# SCH_supercap_2024-08-12.net
KiCad netlist of a schematic drawn in EasyEDA
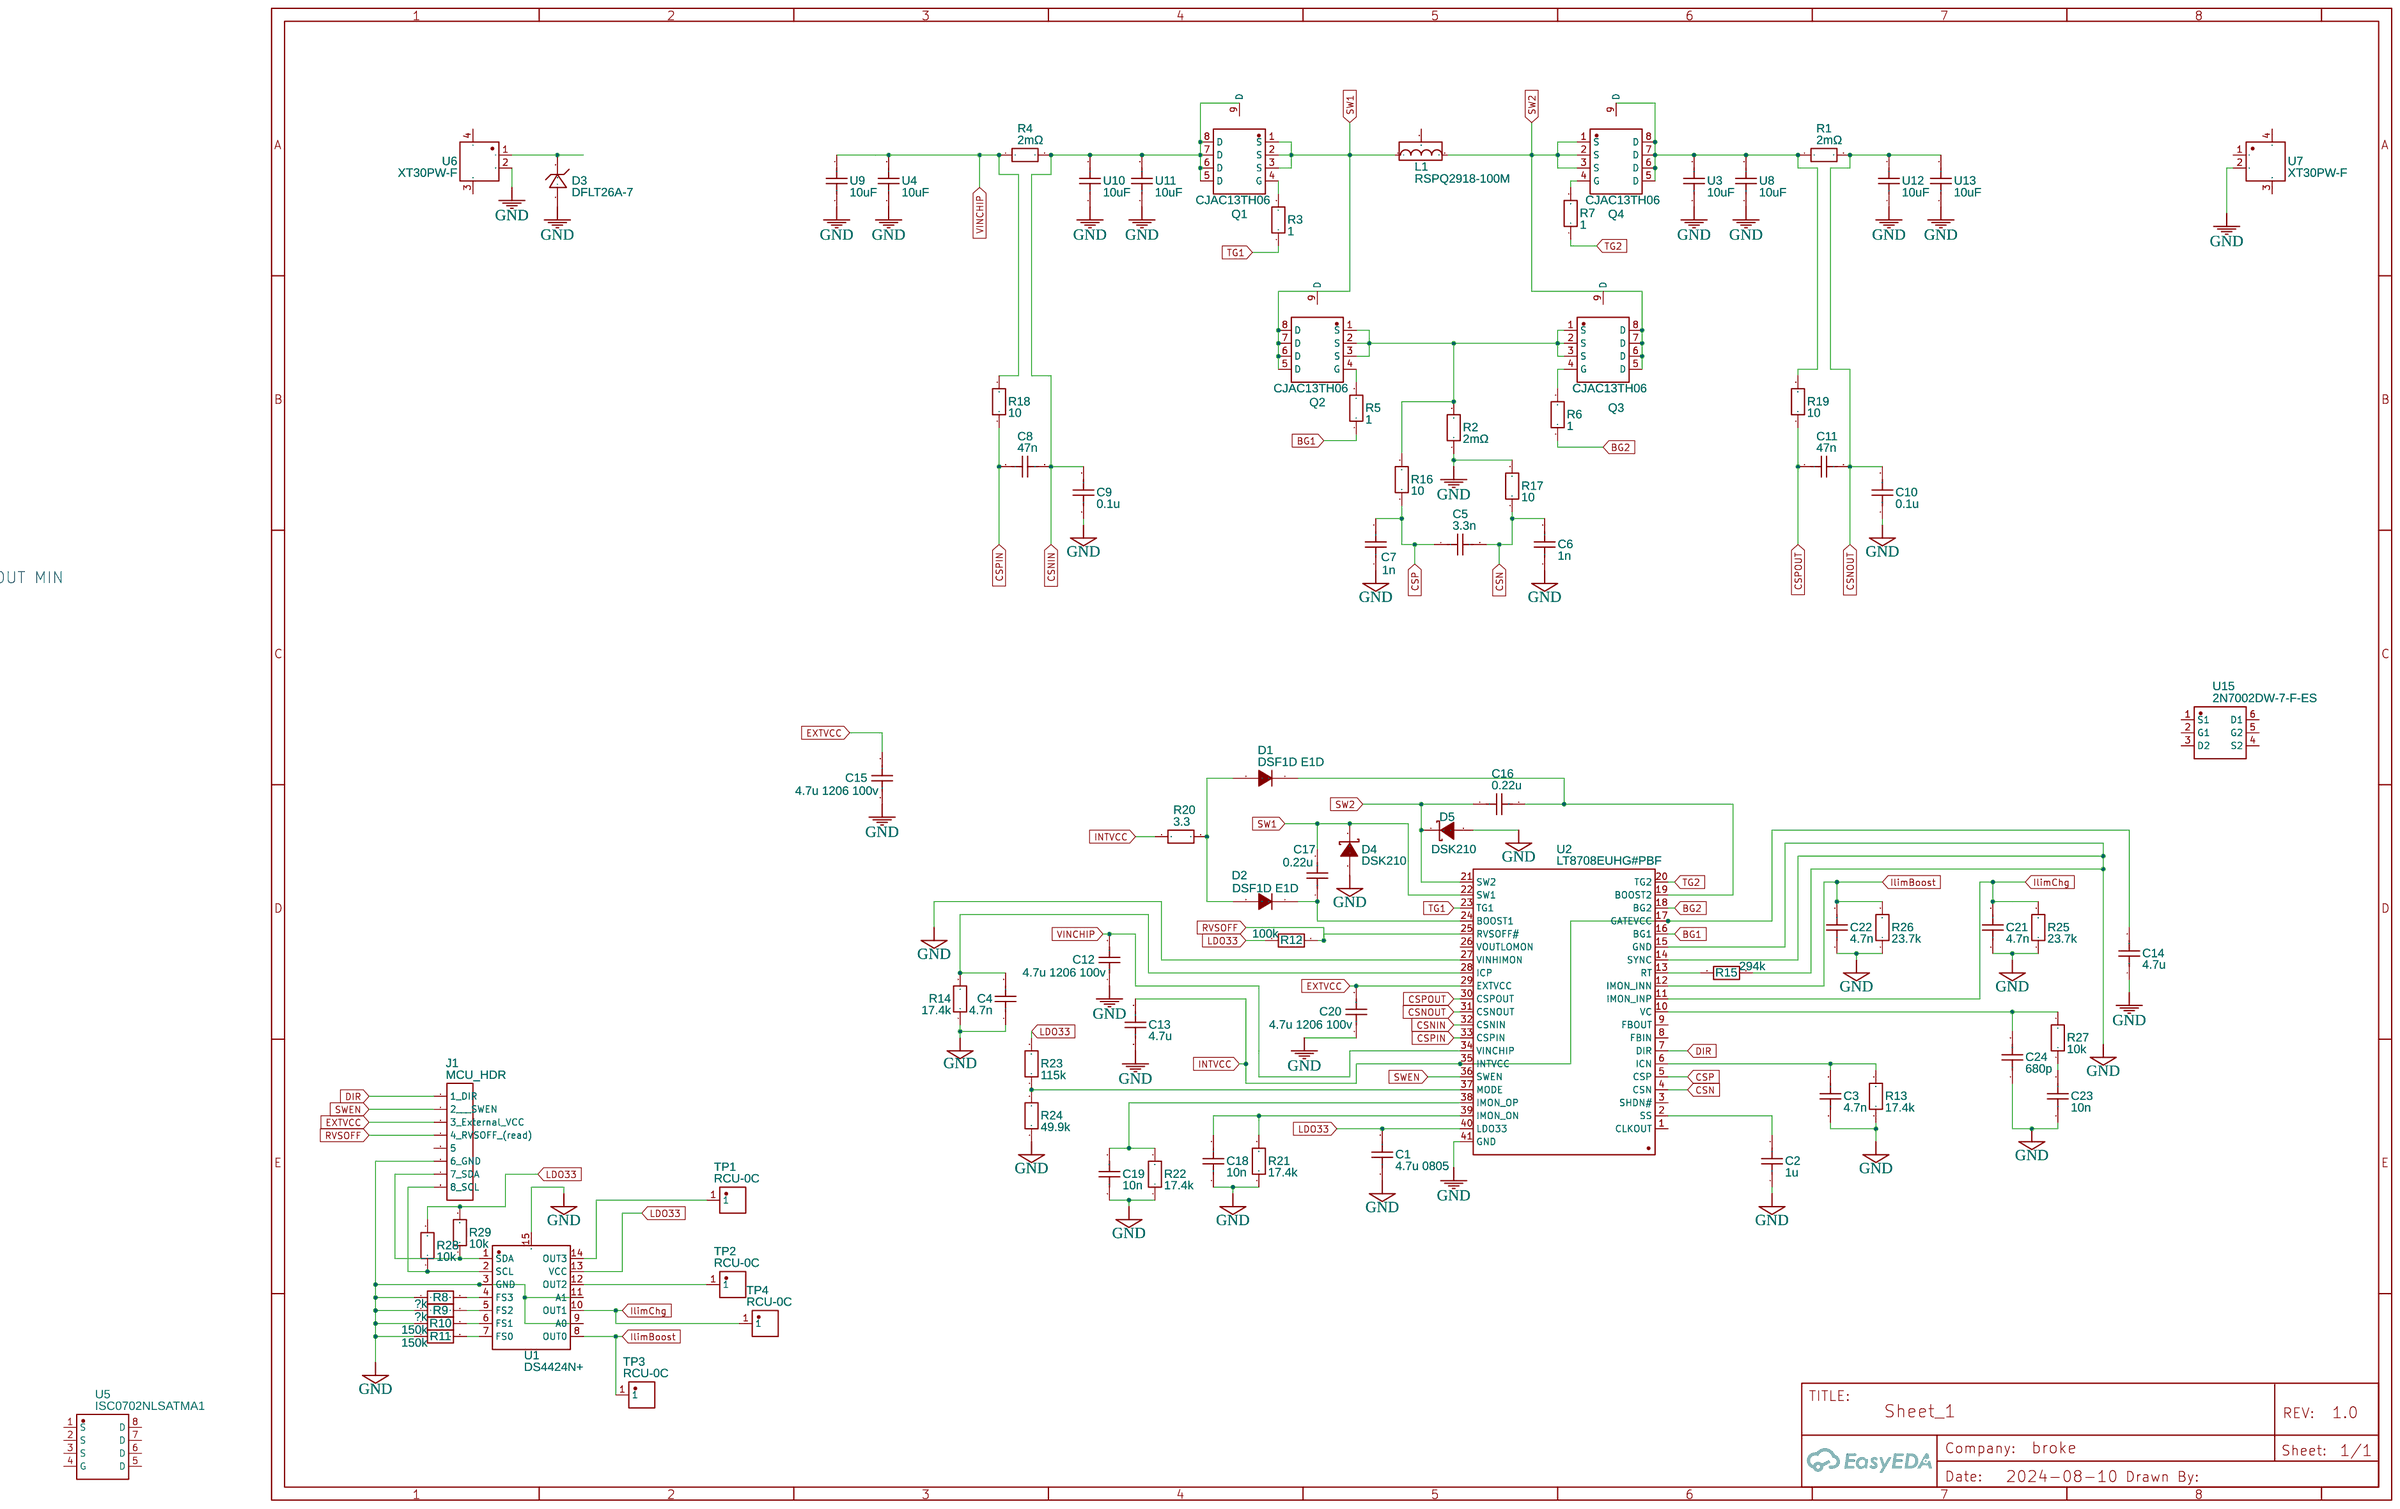
[diagram p0: schematic sheet]

(export (version "E")
  (design (tool "Eeschema 10.0.6"))
  (components
    (comp (ref "C1") (value "4.7u 0805") (libsource (lib "") (part "C_0805_US")))
    (comp (ref "C2") (value "1u") (libsource (lib "") (part "C_0603_US")))
    (comp (ref "C3") (value "4.7n") (libsource (lib "") (part "C_0603_US")))
    (comp (ref "C4") (value "4.7n") (libsource (lib "") (part "C_0603_US_1")))
    (comp (ref "C5") (value "3.3n") (libsource (lib "") (part "C_0603_US_2")))
    (comp (ref "C6") (value "1n") (libsource (lib "") (part "C_0603_US")))
    (comp (ref "C7") (value "1n") (libsource (lib "") (part "C_0603_US")))
    (comp (ref "C8") (value "47n") (libsource (lib "") (part "C_0603_US_2")))
    (comp (ref "C9") (value "0.1u") (libsource (lib "") (part "C_0603_US")))
    (comp (ref "C10") (value "0.1u") (libsource (lib "") (part "C_0603_US")))
    (comp (ref "C11") (value "47n") (libsource (lib "") (part "C_0603_US_2")))
    (comp (ref "C12") (value "4.7u 1206 100v") (libsource (lib "") (part "C_0805_US")))
    (comp (ref "C13") (value "4.7u") (libsource (lib "") (part "C_0603_US")))
    (comp (ref "C14") (value "4.7u") (libsource (lib "") (part "C_0603_US")))
    (comp (ref "C15") (value "4.7u 1206 100v") (libsource (lib "") (part "C_0805_US")))
    (comp (ref "C16") (value "0.22u") (libsource (lib "") (part "C_0603_US_2")))
    (comp (ref "C17") (value "0.22u") (libsource (lib "") (part "C_0603_US")))
    (comp (ref "C18") (value "10n") (libsource (lib "") (part "C_0603_US")))
    (comp (ref "C19") (value "10n") (libsource (lib "") (part "C_0603_US")))
    (comp (ref "C20") (value "4.7u 1206 100v") (libsource (lib "") (part "C_0805_US")))
    (comp (ref "C21") (value "4.7n") (libsource (lib "") (part "C_0603_US")))
    (comp (ref "C22") (value "4.7n") (libsource (lib "") (part "C_0603_US")))
    (comp (ref "C23") (value "10n") (libsource (lib "") (part "C_0603_US")))
    (comp (ref "C24") (value "680p") (libsource (lib "") (part "C_0603_US")))
    (comp (ref "D1")
      (value "DSF1D E1D")
      (fields (field (name "Manufacturer") "MDD(辰达半导体)"))
      (libsource (lib "") (part "DSF1D E1D"))
    )
    (comp (ref "D2")
      (value "DSF1D E1D")
      (fields (field (name "Manufacturer") "MDD(辰达半导体)"))
      (libsource (lib "") (part "DSF1D E1D"))
    )
    (comp (ref "D3")
      (value "DFLT26A-7")
      (fields (field (name "Manufacturer") "DIODES(美台)"))
      (libsource (lib "") (part "DFLT26A-7"))
    )
    (comp (ref "D4")
      (value "DSK210")
      (fields (field (name "Manufacturer") "AnBon(安邦)"))
      (libsource (lib "") (part "DSK210_1"))
    )
    (comp (ref "D5")
      (value "DSK210")
      (fields (field (name "Manufacturer") "AnBon(安邦)"))
      (libsource (lib "") (part "DSK210"))
    )
    (comp (ref "J1") (value "MCU_HDR") (libsource (lib "") (part "HDR-M-2.54_1x8")))
    (comp (ref "L1")
      (value "RSPQ2918-100M")
      (fields (field (name "Manufacturer") "Ruishen(瑞申电子)"))
      (libsource (lib "") (part "RSPQ2918-100M"))
    )
    (comp (ref "Q1")
      (value "CJAC13TH06")
      (fields (field (name "Manufacturer") "CJ(江苏长电/长晶)"))
      (libsource (lib "") (part "CJAC13TH06_1"))
    )
    (comp (ref "Q2")
      (value "CJAC13TH06")
      (fields (field (name "Manufacturer") "CJ(江苏长电/长晶)"))
      (libsource (lib "") (part "CJAC13TH06_1"))
    )
    (comp (ref "Q3")
      (value "CJAC13TH06")
      (fields (field (name "Manufacturer") "CJ(江苏长电/长晶)"))
      (libsource (lib "") (part "CJAC13TH06"))
    )
    (comp (ref "Q4")
      (value "CJAC13TH06")
      (fields (field (name "Manufacturer") "CJ(江苏长电/长晶)"))
      (libsource (lib "") (part "CJAC13TH06"))
    )
    (comp (ref "R1")
      (value "2mΩ")
      (fields (field (name "Manufacturer Part") "FCSL64R002GER") (field (name "Manufacturer") "Ohmite"))
      (libsource (lib "") (part "FCSL64R002GER_1"))
    )
    (comp (ref "R2")
      (value "2mΩ")
      (fields (field (name "Manufacturer Part") "FCSL64R002GER") (field (name "Manufacturer") "Ohmite"))
      (libsource (lib "") (part "FCSL64R002GER"))
    )
    (comp (ref "R3") (value "1") (libsource (lib "") (part "R_0603_EU_1")))
    (comp (ref "R4")
      (value "2mΩ")
      (fields (field (name "Manufacturer Part") "FCSL64R002GER") (field (name "Manufacturer") "Ohmite"))
      (libsource (lib "") (part "FCSL64R002GER_1"))
    )
    (comp (ref "R5") (value "1") (libsource (lib "") (part "R_0603_EU_1")))
    (comp (ref "R6") (value "1") (libsource (lib "") (part "R_0603_EU_1")))
    (comp (ref "R7") (value "1") (libsource (lib "") (part "R_0603_EU_1")))
    (comp (ref "R8") (value "?k") (libsource (lib "") (part "R_0603_EU")))
    (comp (ref "R9") (value "?k") (libsource (lib "") (part "R_0603_EU")))
    (comp (ref "R10") (value "150k") (libsource (lib "") (part "R_0603_EU")))
    (comp (ref "R11") (value "150k") (libsource (lib "") (part "R_0603_EU")))
    (comp (ref "R12") (value "100k") (libsource (lib "") (part "R_0603_EU")))
    (comp (ref "R13") (value "17.4k") (libsource (lib "") (part "R_0603_EU_1")))
    (comp (ref "R14") (value "17.4k") (libsource (lib "") (part "R_0603_EU_1")))
    (comp (ref "R15") (value "294k") (libsource (lib "") (part "R_0603_EU_2")))
    (comp (ref "R16") (value "10") (libsource (lib "") (part "R_0603_EU_1")))
    (comp (ref "R17") (value "10") (libsource (lib "") (part "R_0603_EU_1")))
    (comp (ref "R18") (value "10") (libsource (lib "") (part "R_0603_EU_1")))
    (comp (ref "R19") (value "10") (libsource (lib "") (part "R_0603_EU_1")))
    (comp (ref "R20") (value "3.3") (libsource (lib "") (part "R_0603_EU")))
    (comp (ref "R21") (value "17.4k") (libsource (lib "") (part "R_0603_EU_1")))
    (comp (ref "R22") (value "17.4k") (libsource (lib "") (part "R_0603_EU_1")))
    (comp (ref "R23") (value "115k") (libsource (lib "") (part "R_0603_EU_1")))
    (comp (ref "R24") (value "49.9k") (libsource (lib "") (part "R_0603_EU_1")))
    (comp (ref "R25") (value "23.7k") (libsource (lib "") (part "R_0603_EU_1")))
    (comp (ref "R26") (value "23.7k") (libsource (lib "") (part "R_0603_EU_1")))
    (comp (ref "R27") (value "10k") (libsource (lib "") (part "R_0603_EU_1")))
    (comp (ref "R28") (value "10k") (libsource (lib "") (part "R_0603_EU_1")))
    (comp (ref "R29") (value "10k") (libsource (lib "") (part "R_0603_EU_1")))
    (comp (ref "TP1") (value "RCU-0C") (libsource (lib "") (part "RCU-0C")))
    (comp (ref "TP2") (value "RCU-0C") (libsource (lib "") (part "RCU-0C")))
    (comp (ref "TP3") (value "RCU-0C") (libsource (lib "") (part "RCU-0C")))
    (comp (ref "TP4") (value "RCU-0C") (libsource (lib "") (part "RCU-0C")))
    (comp (ref "U1")
      (value "DS4424N+")
      (fields (field (name "Manufacturer") "ADI(亚德诺)/MAXIM(美信)"))
      (libsource (lib "") (part "DS4424N+"))
    )
    (comp (ref "U2")
      (value "LT8708EUHG#PBF")
      (fields (field (name "Manufacturer") "ADI(亚德诺)"))
      (libsource (lib "") (part "LT8708EUHG#PBF"))
    )
    (comp (ref "U3")
      (value "10uF")
      (fields (field (name "Manufacturer Part") "CKG57NX7R1H106M500JH") (field (name "Manufacturer") "TDK"))
      (libsource (lib "") (part "CKG57NX7R1H106M500JH"))
    )
    (comp (ref "U4")
      (value "10uF")
      (fields (field (name "Manufacturer Part") "CKG57NX7R1H106M500JH") (field (name "Manufacturer") "TDK"))
      (libsource (lib "") (part "CKG57NX7R1H106M500JH"))
    )
    (comp (ref "U5")
      (value "ISC0702NLSATMA1")
      (fields (field (name "Manufacturer") "Infineon(英飞凌)"))
      (libsource (lib "") (part "ISC0702NLSATMA1"))
    )
    (comp (ref "U6")
      (value "XT30PW-F")
      (fields (field (name "Manufacturer Part") "XT30PW-F20.G.Y") (field (name "Manufacturer") "AMASS(艾迈斯)"))
      (libsource (lib "") (part "XT30PW-F_1"))
    )
    (comp (ref "U7")
      (value "XT30PW-F")
      (fields (field (name "Manufacturer Part") "XT30PW-F20.G.Y") (field (name "Manufacturer") "AMASS(艾迈斯)"))
      (libsource (lib "") (part "XT30PW-F"))
    )
    (comp (ref "U8")
      (value "10uF")
      (fields (field (name "Manufacturer Part") "CKG57NX7R1H106M500JH") (field (name "Manufacturer") "TDK"))
      (libsource (lib "") (part "CKG57NX7R1H106M500JH"))
    )
    (comp (ref "U9")
      (value "10uF")
      (fields (field (name "Manufacturer Part") "CKG57NX7R1H106M500JH") (field (name "Manufacturer") "TDK"))
      (libsource (lib "") (part "CKG57NX7R1H106M500JH"))
    )
    (comp (ref "U10")
      (value "10uF")
      (fields (field (name "Manufacturer Part") "CKG57NX7R1H106M500JH") (field (name "Manufacturer") "TDK"))
      (libsource (lib "") (part "CKG57NX7R1H106M500JH"))
    )
    (comp (ref "U11")
      (value "10uF")
      (fields (field (name "Manufacturer Part") "CKG57NX7R1H106M500JH") (field (name "Manufacturer") "TDK"))
      (libsource (lib "") (part "CKG57NX7R1H106M500JH"))
    )
    (comp (ref "U12")
      (value "10uF")
      (fields (field (name "Manufacturer Part") "CKG57NX7R1H106M500JH") (field (name "Manufacturer") "TDK"))
      (libsource (lib "") (part "CKG57NX7R1H106M500JH"))
    )
    (comp (ref "U13")
      (value "10uF")
      (fields (field (name "Manufacturer Part") "CKG57NX7R1H106M500JH") (field (name "Manufacturer") "TDK"))
      (libsource (lib "") (part "CKG57NX7R1H106M500JH"))
    )
    (comp (ref "U15")
      (value "2N7002DW-7-F-ES")
      (fields (field (name "Manufacturer") "ElecSuper(静芯微)"))
      (libsource (lib "") (part "2N7002DW-7-F-ES"))
    )
  )
  (nets
    (net (code "1") (name "BG1") (class "Default")
      (node (ref "R5") (pin "1") (pinfunction "1_1") (pintype "unspecified"))
      (node (ref "U2") (pin "16") (pinfunction "BG1_16") (pintype "unspecified"))
    )
    (net (code "2") (name "BG2") (class "Default")
      (node (ref "R6") (pin "1") (pinfunction "1_1") (pintype "unspecified"))
      (node (ref "U2") (pin "18") (pinfunction "BG2_18") (pintype "unspecified"))
    )
    (net (code "3") (name "CSN") (class "Default")
      (node (ref "C5") (pin "2") (pinfunction "2_2") (pintype "unspecified"))
      (node (ref "C6") (pin "2") (pinfunction "2_2") (pintype "unspecified"))
      (node (ref "R17") (pin "1") (pinfunction "1_1") (pintype "unspecified"))
      (node (ref "U2") (pin "4") (pinfunction "CSN_4") (pintype "unspecified"))
    )
    (net (code "4") (name "CSNIN") (class "Default")
      (node (ref "C8") (pin "2") (pinfunction "2_2") (pintype "unspecified"))
      (node (ref "C9") (pin "2") (pinfunction "2_2") (pintype "unspecified"))
      (node (ref "Q1") (pin "5") (pinfunction "D_5") (pintype "unspecified"))
      (node (ref "Q1") (pin "6") (pinfunction "D_6") (pintype "unspecified"))
      (node (ref "Q1") (pin "7") (pinfunction "D_7") (pintype "unspecified"))
      (node (ref "Q1") (pin "8") (pinfunction "D_8") (pintype "unspecified"))
      (node (ref "R4") (pin "2") (pinfunction "2_2") (pintype "unspecified"))
      (node (ref "U10") (pin "2") (pinfunction "2_2") (pintype "unspecified"))
      (node (ref "U11") (pin "2") (pinfunction "2_2") (pintype "unspecified"))
      (node (ref "U2") (pin "32") (pinfunction "CSNIN_32") (pintype "unspecified"))
    )
    (net (code "5") (name "CSNOUT") (class "Default")
      (node (ref "C10") (pin "2") (pinfunction "2_2") (pintype "unspecified"))
      (node (ref "C11") (pin "2") (pinfunction "2_2") (pintype "unspecified"))
      (node (ref "R1") (pin "2") (pinfunction "2_2") (pintype "unspecified"))
      (node (ref "U12") (pin "2") (pinfunction "2_2") (pintype "unspecified"))
      (node (ref "U13") (pin "2") (pinfunction "2_2") (pintype "unspecified"))
      (node (ref "U2") (pin "31") (pinfunction "CSNOUT_31") (pintype "unspecified"))
    )
    (net (code "6") (name "CSP") (class "Default")
      (node (ref "C5") (pin "1") (pinfunction "1_1") (pintype "unspecified"))
      (node (ref "C7") (pin "2") (pinfunction "2_2") (pintype "unspecified"))
      (node (ref "R16") (pin "1") (pinfunction "1_1") (pintype "unspecified"))
      (node (ref "U2") (pin "5") (pinfunction "CSP_5") (pintype "unspecified"))
    )
    (net (code "7") (name "CSPIN") (class "Default")
      (node (ref "C8") (pin "1") (pinfunction "1_1") (pintype "unspecified"))
      (node (ref "R18") (pin "1") (pinfunction "1_1") (pintype "unspecified"))
      (node (ref "U2") (pin "33") (pinfunction "CSPIN_33") (pintype "unspecified"))
    )
    (net (code "8") (name "CSPOUT") (class "Default")
      (node (ref "C11") (pin "1") (pinfunction "1_1") (pintype "unspecified"))
      (node (ref "R19") (pin "1") (pinfunction "1_1") (pintype "unspecified"))
      (node (ref "U2") (pin "30") (pinfunction "CSPOUT_30") (pintype "unspecified"))
    )
    (net (code "9") (name "DIR") (class "Default")
      (node (ref "J1") (pin "1") (pinfunction "1_DIR_1") (pintype "unspecified"))
      (node (ref "U2") (pin "7") (pinfunction "DIR_7") (pintype "unspecified"))
    )
    (net (code "10") (name "EXTVCC") (class "Default")
      (node (ref "C15") (pin "2") (pinfunction "2_2") (pintype "unspecified"))
      (node (ref "C20") (pin "2") (pinfunction "2_2") (pintype "unspecified"))
      (node (ref "J1") (pin "3") (pinfunction "3_External_VCC_3") (pintype "unspecified"))
      (node (ref "U2") (pin "29") (pinfunction "EXTVCC_29") (pintype "unspecified"))
    )
    (net (code "11") (name "GND") (class "Default")
      (node (ref "C1") (pin "1") (pinfunction "1_1") (pintype "unspecified"))
      (node (ref "C10") (pin "1") (pinfunction "1_1") (pintype "unspecified"))
      (node (ref "C12") (pin "1") (pinfunction "1_1") (pintype "unspecified"))
      (node (ref "C13") (pin "1") (pinfunction "1_1") (pintype "unspecified"))
      (node (ref "C14") (pin "1") (pinfunction "1_1") (pintype "unspecified"))
      (node (ref "C15") (pin "1") (pinfunction "1_1") (pintype "unspecified"))
      (node (ref "C18") (pin "1") (pinfunction "1_1") (pintype "unspecified"))
      (node (ref "C19") (pin "1") (pinfunction "1_1") (pintype "unspecified"))
      (node (ref "C2") (pin "1") (pinfunction "1_1") (pintype "unspecified"))
      (node (ref "C20") (pin "1") (pinfunction "1_1") (pintype "unspecified"))
      (node (ref "C21") (pin "1") (pinfunction "1_1") (pintype "unspecified"))
      (node (ref "C22") (pin "1") (pinfunction "1_1") (pintype "unspecified"))
      (node (ref "C23") (pin "1") (pinfunction "1_1") (pintype "unspecified"))
      (node (ref "C24") (pin "1") (pinfunction "1_1") (pintype "unspecified"))
      (node (ref "C3") (pin "1") (pinfunction "1_1") (pintype "unspecified"))
      (node (ref "C4") (pin "1") (pinfunction "1_1") (pintype "unspecified"))
      (node (ref "C6") (pin "1") (pinfunction "1_1") (pintype "unspecified"))
      (node (ref "C7") (pin "1") (pinfunction "1_1") (pintype "unspecified"))
      (node (ref "C9") (pin "1") (pinfunction "1_1") (pintype "unspecified"))
      (node (ref "D3") (pin "2") (pinfunction "A_2") (pintype "unspecified"))
      (node (ref "D4") (pin "2") (pinfunction "A_2") (pintype "unspecified"))
      (node (ref "D5") (pin "2") (pinfunction "A_2") (pintype "unspecified"))
      (node (ref "J1") (pin "6") (pinfunction "6_GND_6") (pintype "unspecified"))
      (node (ref "R10") (pin "1") (pinfunction "1_1") (pintype "unspecified"))
      (node (ref "R11") (pin "1") (pinfunction "1_1") (pintype "unspecified"))
      (node (ref "R13") (pin "1") (pinfunction "1_1") (pintype "unspecified"))
      (node (ref "R14") (pin "1") (pinfunction "1_1") (pintype "unspecified"))
      (node (ref "R15") (pin "1") (pinfunction "1_1") (pintype "unspecified"))
      (node (ref "R17") (pin "2") (pinfunction "2_2") (pintype "unspecified"))
      (node (ref "R2") (pin "1") (pinfunction "1_1") (pintype "unspecified"))
      (node (ref "R21") (pin "1") (pinfunction "1_1") (pintype "unspecified"))
      (node (ref "R22") (pin "1") (pinfunction "1_1") (pintype "unspecified"))
      (node (ref "R24") (pin "1") (pinfunction "1_1") (pintype "unspecified"))
      (node (ref "R25") (pin "1") (pinfunction "1_1") (pintype "unspecified"))
      (node (ref "R26") (pin "1") (pinfunction "1_1") (pintype "unspecified"))
      (node (ref "R8") (pin "1") (pinfunction "1_1") (pintype "unspecified"))
      (node (ref "R9") (pin "1") (pinfunction "1_1") (pintype "unspecified"))
      (node (ref "U1") (pin "11") (pinfunction "A1_11") (pintype "unspecified"))
      (node (ref "U1") (pin "15") (pinfunction "EP_15") (pintype "unspecified"))
      (node (ref "U1") (pin "3") (pinfunction "GND_3") (pintype "unspecified"))
      (node (ref "U1") (pin "9") (pinfunction "A0_9") (pintype "unspecified"))
      (node (ref "U10") (pin "1") (pinfunction "1_1") (pintype "unspecified"))
      (node (ref "U11") (pin "1") (pinfunction "1_1") (pintype "unspecified"))
      (node (ref "U12") (pin "1") (pinfunction "1_1") (pintype "unspecified"))
      (node (ref "U13") (pin "1") (pinfunction "1_1") (pintype "unspecified"))
      (node (ref "U2") (pin "14") (pinfunction "SYNC_14") (pintype "unspecified"))
      (node (ref "U2") (pin "15") (pinfunction "GND_15") (pintype "unspecified"))
      (node (ref "U2") (pin "27") (pinfunction "VINHIMON_27") (pintype "unspecified"))
      (node (ref "U2") (pin "41") (pinfunction "GND_41") (pintype "unspecified"))
      (node (ref "U3") (pin "1") (pinfunction "1_1") (pintype "unspecified"))
      (node (ref "U4") (pin "1") (pinfunction "1_1") (pintype "unspecified"))
      (node (ref "U6") (pin "2") (pinfunction "2_2") (pintype "unspecified"))
      (node (ref "U7") (pin "2") (pinfunction "2_2") (pintype "unspecified"))
      (node (ref "U8") (pin "1") (pinfunction "1_1") (pintype "unspecified"))
      (node (ref "U9") (pin "1") (pinfunction "1_1") (pintype "unspecified"))
    )
    (net (code "12") (name "INTVCC") (class "Default")
      (node (ref "C13") (pin "2") (pinfunction "2_2") (pintype "unspecified"))
      (node (ref "C14") (pin "2") (pinfunction "2_2") (pintype "unspecified"))
      (node (ref "R20") (pin "1") (pinfunction "1_1") (pintype "unspecified"))
      (node (ref "U2") (pin "17") (pinfunction "GATEVCC_17") (pintype "unspecified"))
      (node (ref "U2") (pin "35") (pinfunction "INTVCC_35") (pintype "unspecified"))
    )
    (net (code "13") (name "IlimBoost") (class "Default")
      (node (ref "C22") (pin "2") (pinfunction "2_2") (pintype "unspecified"))
      (node (ref "R26") (pin "2") (pinfunction "2_2") (pintype "unspecified"))
      (node (ref "TP3") (pin "1") (pinfunction "1_1") (pintype "unspecified"))
      (node (ref "U1") (pin "8") (pinfunction "OUT0_8") (pintype "unspecified"))
      (node (ref "U2") (pin "12") (pinfunction "IMON_INN_12") (pintype "unspecified"))
    )
    (net (code "14") (name "IlimChg") (class "Default")
      (node (ref "C21") (pin "2") (pinfunction "2_2") (pintype "unspecified"))
      (node (ref "R25") (pin "2") (pinfunction "2_2") (pintype "unspecified"))
      (node (ref "TP4") (pin "1") (pinfunction "1_1") (pintype "unspecified"))
      (node (ref "U1") (pin "10") (pinfunction "OUT1_10") (pintype "unspecified"))
      (node (ref "U2") (pin "11") (pinfunction "IMON_INP_11") (pintype "unspecified"))
    )
    (net (code "15") (name "LDO33") (class "Default")
      (node (ref "C1") (pin "2") (pinfunction "2_2") (pintype "unspecified"))
      (node (ref "R12") (pin "1") (pinfunction "1_1") (pintype "unspecified"))
      (node (ref "R23") (pin "2") (pinfunction "2_2") (pintype "unspecified"))
      (node (ref "R28") (pin "2") (pinfunction "2_2") (pintype "unspecified"))
      (node (ref "R29") (pin "2") (pinfunction "2_2") (pintype "unspecified"))
      (node (ref "U1") (pin "13") (pinfunction "VCC_13") (pintype "unspecified"))
      (node (ref "U2") (pin "40") (pinfunction "LDO33_40") (pintype "unspecified"))
    )
    (net (code "16") (name "Net-(C23-Pad2)") (class "Default")
      (node (ref "C23") (pin "2") (pinfunction "2_2") (pintype "unspecified"))
      (node (ref "R27") (pin "1") (pinfunction "1_1") (pintype "unspecified"))
    )
    (net (code "17") (name "Net-(D1-Pad2)") (class "Default")
      (node (ref "D1") (pin "2") (pinfunction "2_2") (pintype "unspecified"))
      (node (ref "D2") (pin "2") (pinfunction "2_2") (pintype "unspecified"))
      (node (ref "R20") (pin "2") (pinfunction "2_2") (pintype "unspecified"))
    )
    (net (code "18") (name "Net-(D3-C)") (class "Default")
      (node (ref "D3") (pin "1") (pinfunction "C_1") (pintype "unspecified"))
      (node (ref "U6") (pin "1") (pinfunction "1_1") (pintype "unspecified"))
    )
    (net (code "19") (name "Net-(J1-7_SDA)") (class "Default")
      (node (ref "J1") (pin "7") (pinfunction "7_SDA_7") (pintype "unspecified"))
      (node (ref "R29") (pin "1") (pinfunction "1_1") (pintype "unspecified"))
      (node (ref "U1") (pin "1") (pinfunction "SDA_1") (pintype "unspecified"))
    )
    (net (code "20") (name "Net-(J1-8_SCL)") (class "Default")
      (node (ref "J1") (pin "8") (pinfunction "8_SCL_8") (pintype "unspecified"))
      (node (ref "R28") (pin "1") (pinfunction "1_1") (pintype "unspecified"))
      (node (ref "U1") (pin "2") (pinfunction "SCL_2") (pintype "unspecified"))
    )
    (net (code "21") (name "Net-(Q1-G)") (class "Default")
      (node (ref "Q1") (pin "4") (pinfunction "G_4") (pintype "unspecified"))
      (node (ref "R3") (pin "2") (pinfunction "2_2") (pintype "unspecified"))
    )
    (net (code "22") (name "Net-(Q2-G)") (class "Default")
      (node (ref "Q2") (pin "4") (pinfunction "G_4") (pintype "unspecified"))
      (node (ref "R5") (pin "2") (pinfunction "2_2") (pintype "unspecified"))
    )
    (net (code "23") (name "Net-(Q2-S-Pad1)") (class "Default")
      (node (ref "Q2") (pin "1") (pinfunction "S_1") (pintype "unspecified"))
      (node (ref "Q2") (pin "2") (pinfunction "S_2") (pintype "unspecified"))
      (node (ref "Q2") (pin "3") (pinfunction "S_3") (pintype "unspecified"))
      (node (ref "Q3") (pin "1") (pinfunction "S_1") (pintype "unspecified"))
      (node (ref "Q3") (pin "2") (pinfunction "S_2") (pintype "unspecified"))
      (node (ref "Q3") (pin "3") (pinfunction "S_3") (pintype "unspecified"))
      (node (ref "R16") (pin "2") (pinfunction "2_2") (pintype "unspecified"))
      (node (ref "R2") (pin "2") (pinfunction "2_2") (pintype "unspecified"))
    )
    (net (code "24") (name "Net-(Q3-G)") (class "Default")
      (node (ref "Q3") (pin "4") (pinfunction "G_4") (pintype "unspecified"))
      (node (ref "R6") (pin "2") (pinfunction "2_2") (pintype "unspecified"))
    )
    (net (code "25") (name "Net-(Q4-D-Pad5)") (class "Default")
      (node (ref "Q4") (pin "5") (pinfunction "D_5") (pintype "unspecified"))
      (node (ref "Q4") (pin "6") (pinfunction "D_6") (pintype "unspecified"))
      (node (ref "Q4") (pin "7") (pinfunction "D_7") (pintype "unspecified"))
      (node (ref "Q4") (pin "8") (pinfunction "D_8") (pintype "unspecified"))
      (node (ref "R1") (pin "1") (pinfunction "1_1") (pintype "unspecified"))
      (node (ref "R19") (pin "2") (pinfunction "2_2") (pintype "unspecified"))
      (node (ref "U3") (pin "2") (pinfunction "2_2") (pintype "unspecified"))
      (node (ref "U8") (pin "2") (pinfunction "2_2") (pintype "unspecified"))
    )
    (net (code "26") (name "Net-(Q4-G)") (class "Default")
      (node (ref "Q4") (pin "4") (pinfunction "G_4") (pintype "unspecified"))
      (node (ref "R7") (pin "2") (pinfunction "2_2") (pintype "unspecified"))
    )
    (net (code "27") (name "Net-(U1-FS0)") (class "Default")
      (node (ref "R11") (pin "2") (pinfunction "2_2") (pintype "unspecified"))
      (node (ref "U1") (pin "7") (pinfunction "FS0_7") (pintype "unspecified"))
    )
    (net (code "28") (name "Net-(U1-FS1)") (class "Default")
      (node (ref "R10") (pin "2") (pinfunction "2_2") (pintype "unspecified"))
      (node (ref "U1") (pin "6") (pinfunction "FS1_6") (pintype "unspecified"))
    )
    (net (code "29") (name "Net-(U1-FS2)") (class "Default")
      (node (ref "R9") (pin "2") (pinfunction "2_2") (pintype "unspecified"))
      (node (ref "U1") (pin "5") (pinfunction "FS2_5") (pintype "unspecified"))
    )
    (net (code "30") (name "Net-(U1-FS3)") (class "Default")
      (node (ref "R8") (pin "2") (pinfunction "2_2") (pintype "unspecified"))
      (node (ref "U1") (pin "4") (pinfunction "FS3_4") (pintype "unspecified"))
    )
    (net (code "31") (name "Net-(U1-OUT2)") (class "Default")
      (node (ref "TP2") (pin "1") (pinfunction "1_1") (pintype "unspecified"))
      (node (ref "U1") (pin "12") (pinfunction "OUT2_12") (pintype "unspecified"))
    )
    (net (code "32") (name "Net-(U1-OUT3)") (class "Default")
      (node (ref "TP1") (pin "1") (pinfunction "1_1") (pintype "unspecified"))
      (node (ref "U1") (pin "14") (pinfunction "OUT3_14") (pintype "unspecified"))
    )
    (net (code "33") (name "Net-(U2-BOOST1)") (class "Default")
      (node (ref "C17") (pin "1") (pinfunction "1_1") (pintype "unspecified"))
      (node (ref "D2") (pin "1") (pinfunction "1_1") (pintype "unspecified"))
      (node (ref "U2") (pin "24") (pinfunction "BOOST1_24") (pintype "unspecified"))
    )
    (net (code "34") (name "Net-(U2-BOOST2)") (class "Default")
      (node (ref "C16") (pin "2") (pinfunction "2_2") (pintype "unspecified"))
      (node (ref "D1") (pin "1") (pinfunction "1_1") (pintype "unspecified"))
      (node (ref "U2") (pin "19") (pinfunction "BOOST2_19") (pintype "unspecified"))
    )
    (net (code "35") (name "Net-(U2-ICN)") (class "Default")
      (node (ref "C3") (pin "2") (pinfunction "2_2") (pintype "unspecified"))
      (node (ref "R13") (pin "2") (pinfunction "2_2") (pintype "unspecified"))
      (node (ref "U2") (pin "6") (pinfunction "ICN_6") (pintype "unspecified"))
    )
    (net (code "36") (name "Net-(U2-ICP)") (class "Default")
      (node (ref "C4") (pin "2") (pinfunction "2_2") (pintype "unspecified"))
      (node (ref "R14") (pin "2") (pinfunction "2_2") (pintype "unspecified"))
      (node (ref "U2") (pin "28") (pinfunction "ICP_28") (pintype "unspecified"))
    )
    (net (code "37") (name "Net-(U2-IMON_ON)") (class "Default")
      (node (ref "C18") (pin "2") (pinfunction "2_2") (pintype "unspecified"))
      (node (ref "R21") (pin "2") (pinfunction "2_2") (pintype "unspecified"))
      (node (ref "U2") (pin "39") (pinfunction "IMON_ON_39") (pintype "unspecified"))
    )
    (net (code "38") (name "Net-(U2-IMON_OP)") (class "Default")
      (node (ref "C19") (pin "2") (pinfunction "2_2") (pintype "unspecified"))
      (node (ref "R22") (pin "2") (pinfunction "2_2") (pintype "unspecified"))
      (node (ref "U2") (pin "38") (pinfunction "IMON_OP_38") (pintype "unspecified"))
    )
    (net (code "39") (name "Net-(U2-MODE)") (class "Default")
      (node (ref "R23") (pin "1") (pinfunction "1_1") (pintype "unspecified"))
      (node (ref "R24") (pin "2") (pinfunction "2_2") (pintype "unspecified"))
      (node (ref "U2") (pin "37") (pinfunction "MODE_37") (pintype "unspecified"))
    )
    (net (code "40") (name "Net-(U2-RT)") (class "Default")
      (node (ref "R15") (pin "2") (pinfunction "2_2") (pintype "unspecified"))
      (node (ref "U2") (pin "13") (pinfunction "RT_13") (pintype "unspecified"))
    )
    (net (code "41") (name "Net-(U2-SS)") (class "Default")
      (node (ref "C2") (pin "2") (pinfunction "2_2") (pintype "unspecified"))
      (node (ref "U2") (pin "2") (pinfunction "SS_2") (pintype "unspecified"))
    )
    (net (code "42") (name "Net-(U2-VC)") (class "Default")
      (node (ref "C24") (pin "2") (pinfunction "2_2") (pintype "unspecified"))
      (node (ref "R27") (pin "2") (pinfunction "2_2") (pintype "unspecified"))
      (node (ref "U2") (pin "10") (pinfunction "VC_10") (pintype "unspecified"))
    )
    (net (code "43") (name "RVSOFF") (class "Default")
      (node (ref "J1") (pin "4") (pinfunction "4_RVSOFF_(read)_4") (pintype "unspecified"))
      (node (ref "R12") (pin "2") (pinfunction "2_2") (pintype "unspecified"))
      (node (ref "U2") (pin "25") (pinfunction "RVSOFF#_25") (pintype "unspecified"))
    )
    (net (code "44") (name "SW1") (class "Default")
      (node (ref "C17") (pin "2") (pinfunction "2_2") (pintype "unspecified"))
      (node (ref "D4") (pin "1") (pinfunction "C_1") (pintype "unspecified"))
      (node (ref "L1") (pin "1") (pinfunction "1_1") (pintype "unspecified"))
      (node (ref "Q1") (pin "1") (pinfunction "S_1") (pintype "unspecified"))
      (node (ref "Q1") (pin "2") (pinfunction "S_2") (pintype "unspecified"))
      (node (ref "Q1") (pin "3") (pinfunction "S_3") (pintype "unspecified"))
      (node (ref "Q2") (pin "5") (pinfunction "D_5") (pintype "unspecified"))
      (node (ref "Q2") (pin "6") (pinfunction "D_6") (pintype "unspecified"))
      (node (ref "Q2") (pin "7") (pinfunction "D_7") (pintype "unspecified"))
      (node (ref "Q2") (pin "8") (pinfunction "D_8") (pintype "unspecified"))
      (node (ref "U2") (pin "22") (pinfunction "SW1_22") (pintype "unspecified"))
    )
    (net (code "45") (name "SW2") (class "Default")
      (node (ref "C16") (pin "1") (pinfunction "1_1") (pintype "unspecified"))
      (node (ref "D5") (pin "1") (pinfunction "C_1") (pintype "unspecified"))
      (node (ref "L1") (pin "2") (pinfunction "2_2") (pintype "unspecified"))
      (node (ref "Q3") (pin "5") (pinfunction "D_5") (pintype "unspecified"))
      (node (ref "Q3") (pin "6") (pinfunction "D_6") (pintype "unspecified"))
      (node (ref "Q3") (pin "7") (pinfunction "D_7") (pintype "unspecified"))
      (node (ref "Q3") (pin "8") (pinfunction "D_8") (pintype "unspecified"))
      (node (ref "Q4") (pin "1") (pinfunction "S_1") (pintype "unspecified"))
      (node (ref "Q4") (pin "2") (pinfunction "S_2") (pintype "unspecified"))
      (node (ref "Q4") (pin "3") (pinfunction "S_3") (pintype "unspecified"))
      (node (ref "U2") (pin "21") (pinfunction "SW2_21") (pintype "unspecified"))
    )
    (net (code "46") (name "SWEN") (class "Default")
      (node (ref "J1") (pin "2") (pinfunction "2___SWEN_2") (pintype "unspecified"))
      (node (ref "U2") (pin "36") (pinfunction "SWEN_36") (pintype "unspecified"))
    )
    (net (code "47") (name "TG1") (class "Default")
      (node (ref "R3") (pin "1") (pinfunction "1_1") (pintype "unspecified"))
      (node (ref "U2") (pin "23") (pinfunction "TG1_23") (pintype "unspecified"))
    )
    (net (code "48") (name "TG2") (class "Default")
      (node (ref "R7") (pin "1") (pinfunction "1_1") (pintype "unspecified"))
      (node (ref "U2") (pin "20") (pinfunction "TG2_20") (pintype "unspecified"))
    )
    (net (code "49") (name "VINCHIP") (class "Default")
      (node (ref "C12") (pin "2") (pinfunction "2_2") (pintype "unspecified"))
      (node (ref "R18") (pin "2") (pinfunction "2_2") (pintype "unspecified"))
      (node (ref "R4") (pin "1") (pinfunction "1_1") (pintype "unspecified"))
      (node (ref "U2") (pin "34") (pinfunction "VINCHIP_34") (pintype "unspecified"))
      (node (ref "U4") (pin "2") (pinfunction "2_2") (pintype "unspecified"))
      (node (ref "U9") (pin "2") (pinfunction "2_2") (pintype "unspecified"))
    )
    (net (code "50") (name "unconnected-(J1-Pad5)") (class "Default")
      (node (ref "J1") (pin "5") (pinfunction "5_5") (pintype "unspecified"))
    )
    (net (code "51") (name "unconnected-(L1-NC-Pad3)") (class "Default")
      (node (ref "L1") (pin "3") (pinfunction "NC_3") (pintype "unspecified"))
    )
    (net (code "52") (name "unconnected-(Q1-D-Pad9)") (class "Default")
      (node (ref "Q1") (pin "9") (pinfunction "D_9") (pintype "unspecified"))
    )
    (net (code "53") (name "unconnected-(Q2-D-Pad9)") (class "Default")
      (node (ref "Q2") (pin "9") (pinfunction "D_9") (pintype "unspecified"))
    )
    (net (code "54") (name "unconnected-(Q3-D-Pad9)") (class "Default")
      (node (ref "Q3") (pin "9") (pinfunction "D_9") (pintype "unspecified"))
    )
    (net (code "55") (name "unconnected-(Q4-D-Pad9)") (class "Default")
      (node (ref "Q4") (pin "9") (pinfunction "D_9") (pintype "unspecified"))
    )
    (net (code "56") (name "unconnected-(U2-CLKOUT-Pad1)") (class "Default")
      (node (ref "U2") (pin "1") (pinfunction "CLKOUT_1") (pintype "unspecified"))
    )
    (net (code "57") (name "unconnected-(U2-FBIN-Pad8)") (class "Default")
      (node (ref "U2") (pin "8") (pinfunction "FBIN_8") (pintype "unspecified"))
    )
    (net (code "58") (name "unconnected-(U2-FBOUT-Pad9)") (class "Default")
      (node (ref "U2") (pin "9") (pinfunction "FBOUT_9") (pintype "unspecified"))
    )
    (net (code "59") (name "unconnected-(U2-SHDN#-Pad3)") (class "Default")
      (node (ref "U2") (pin "3") (pinfunction "SHDN#_3") (pintype "unspecified"))
    )
    (net (code "60") (name "unconnected-(U2-VOUTLOMON-Pad26)") (class "Default")
      (node (ref "U2") (pin "26") (pinfunction "VOUTLOMON_26") (pintype "unspecified"))
    )
    (net (code "61") (name "unconnected-(U5-D-Pad5)") (class "Default")
      (node (ref "U5") (pin "5") (pinfunction "D_5") (pintype "unspecified"))
    )
    (net (code "62") (name "unconnected-(U5-D-Pad6)") (class "Default")
      (node (ref "U5") (pin "6") (pinfunction "D_6") (pintype "unspecified"))
    )
    (net (code "63") (name "unconnected-(U5-D-Pad7)") (class "Default")
      (node (ref "U5") (pin "7") (pinfunction "D_7") (pintype "unspecified"))
    )
    (net (code "64") (name "unconnected-(U5-D-Pad8)") (class "Default")
      (node (ref "U5") (pin "8") (pinfunction "D_8") (pintype "unspecified"))
    )
    (net (code "65") (name "unconnected-(U5-G-Pad4)") (class "Default")
      (node (ref "U5") (pin "4") (pinfunction "G_4") (pintype "unspecified"))
    )
    (net (code "66") (name "unconnected-(U5-S-Pad1)") (class "Default")
      (node (ref "U5") (pin "1") (pinfunction "S_1") (pintype "unspecified"))
    )
    (net (code "67") (name "unconnected-(U5-S-Pad2)") (class "Default")
      (node (ref "U5") (pin "2") (pinfunction "S_2") (pintype "unspecified"))
    )
    (net (code "68") (name "unconnected-(U5-S-Pad3)") (class "Default")
      (node (ref "U5") (pin "3") (pinfunction "S_3") (pintype "unspecified"))
    )
    (net (code "69") (name "unconnected-(U6-Pad3)") (class "Default")
      (node (ref "U6") (pin "3") (pinfunction "3_3") (pintype "unspecified"))
    )
    (net (code "70") (name "unconnected-(U6-Pad4)") (class "Default")
      (node (ref "U6") (pin "4") (pinfunction "4_4") (pintype "unspecified"))
    )
    (net (code "71") (name "unconnected-(U7-Pad1)") (class "Default")
      (node (ref "U7") (pin "1") (pinfunction "1_1") (pintype "unspecified"))
    )
    (net (code "72") (name "unconnected-(U7-Pad3)") (class "Default")
      (node (ref "U7") (pin "3") (pinfunction "3_3") (pintype "unspecified"))
    )
    (net (code "73") (name "unconnected-(U7-Pad4)") (class "Default")
      (node (ref "U7") (pin "4") (pinfunction "4_4") (pintype "unspecified"))
    )
    (net (code "74") (name "unconnected-(U15-D1-Pad6)") (class "Default")
      (node (ref "U15") (pin "6") (pinfunction "D1_6") (pintype "unspecified"))
    )
    (net (code "75") (name "unconnected-(U15-D2-Pad3)") (class "Default")
      (node (ref "U15") (pin "3") (pinfunction "D2_3") (pintype "unspecified"))
    )
    (net (code "76") (name "unconnected-(U15-G1-Pad2)") (class "Default")
      (node (ref "U15") (pin "2") (pinfunction "G1_2") (pintype "unspecified"))
    )
    (net (code "77") (name "unconnected-(U15-G2-Pad5)") (class "Default")
      (node (ref "U15") (pin "5") (pinfunction "G2_5") (pintype "unspecified"))
    )
    (net (code "78") (name "unconnected-(U15-S1-Pad1)") (class "Default")
      (node (ref "U15") (pin "1") (pinfunction "S1_1") (pintype "unspecified"))
    )
    (net (code "79") (name "unconnected-(U15-S2-Pad4)") (class "Default")
      (node (ref "U15") (pin "4") (pinfunction "S2_4") (pintype "unspecified"))
    )
  )
)
